# RGBLEDMatrixBPack.net
KiCad netlist of a schematic drawn in EAGLE
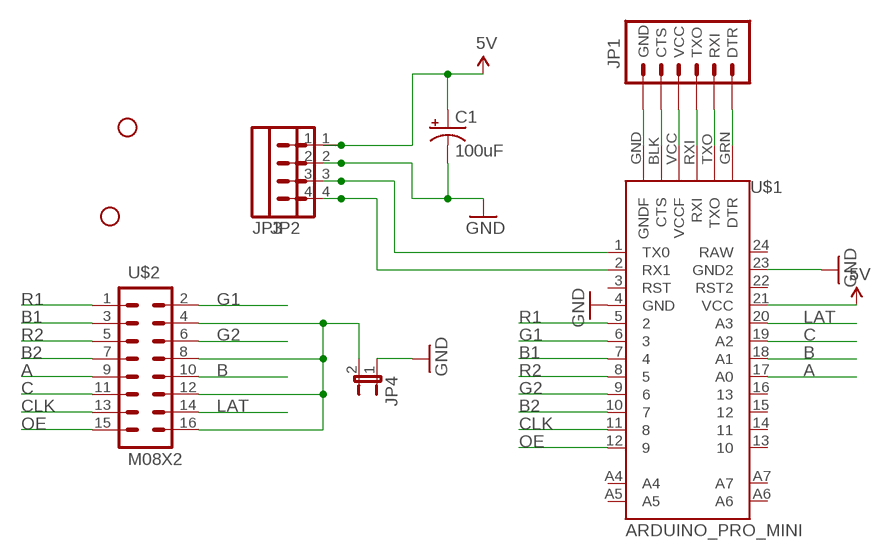
[diagram p0: schematic, sheet 1]

(export (version "E")
  (design (tool "Eeschema 10.0.6"))
  (components
    (comp (ref "C1")
      (value "100uF")
      (footprint "eagle-import:CPOL-RADIAL-100UF-25V")
      (libsource (lib "eagle-import") (part "CAP_POLPTH1"))
    )
    (comp (ref "JP1")
      (value "ARDUINO_SERIAL_PROGRAMPTH")
      (footprint "eagle-import:1X06")
      (libsource (lib "eagle-import") (part "ARDUINO_SERIAL_PROGRAMPTH"))
    )
    (comp (ref "JP2")
      (value "M04JST-PTH")
      (footprint "eagle-import:JST-4-PTH")
      (libsource (lib "eagle-import") (part "M04JST-PTH"))
    )
    (comp (ref "JP3")
      (value "M04JST-PTH")
      (footprint "eagle-import:JST-4-PTH")
      (libsource (lib "eagle-import") (part "M04JST-PTH"))
    )
    (comp (ref "JP4")
      (value "JUMPER-2SMD-NO")
      (footprint "eagle-import:SJ_2S-NO")
      (libsource (lib "eagle-import") (part "JUMPER-2SMD-NO"))
    )
    (comp (ref "STANDOFF1")
      (value "STAND-OFF")
      (footprint "eagle-import:STAND-OFF")
      (libsource (lib "eagle-import") (part "STAND-OFF"))
    )
    (comp (ref "STANDOFF2")
      (value "STAND-OFF")
      (footprint "eagle-import:STAND-OFF")
      (libsource (lib "eagle-import") (part "STAND-OFF"))
    )
    (comp (ref "U$1")
      (value "ARDUINO_PRO_MINI")
      (footprint "eagle-import:ARDUINO_PRO_MINI")
      (libsource (lib "eagle-import") (part "ARDUINO_PRO_MINI"))
    )
    (comp (ref "U$2")
      (value "M08X2")
      (footprint "eagle-import:2X8")
      (libsource (lib "eagle-import") (part "M08X2"))
    )
  )
  (nets
    (net (code "1") (name "/A") (class "Default")
      (node (ref "U$1") (pin "17") (pinfunction "A0_17") (pintype "bidirectional"))
      (node (ref "U$2") (pin "9") (pinfunction "9_9") (pintype "passive"))
    )
    (net (code "2") (name "/B") (class "Default")
      (node (ref "U$1") (pin "18") (pinfunction "A1_18") (pintype "bidirectional"))
      (node (ref "U$2") (pin "10") (pinfunction "10_10") (pintype "passive"))
    )
    (net (code "3") (name "/B1") (class "Default")
      (node (ref "U$1") (pin "7") (pinfunction "4_7") (pintype "bidirectional"))
      (node (ref "U$2") (pin "3") (pinfunction "3_3") (pintype "passive"))
    )
    (net (code "4") (name "/B2") (class "Default")
      (node (ref "U$1") (pin "10") (pinfunction "7_10") (pintype "bidirectional"))
      (node (ref "U$2") (pin "7") (pinfunction "7_7") (pintype "passive"))
    )
    (net (code "5") (name "/C") (class "Default")
      (node (ref "U$1") (pin "19") (pinfunction "A2_19") (pintype "bidirectional"))
      (node (ref "U$2") (pin "11") (pinfunction "11_11") (pintype "passive"))
    )
    (net (code "6") (name "/CLK") (class "Default")
      (node (ref "U$1") (pin "11") (pinfunction "8_11") (pintype "bidirectional"))
      (node (ref "U$2") (pin "13") (pinfunction "13_13") (pintype "passive"))
    )
    (net (code "7") (name "/G1") (class "Default")
      (node (ref "U$1") (pin "6") (pinfunction "3_6") (pintype "bidirectional"))
      (node (ref "U$2") (pin "2") (pinfunction "2_2") (pintype "passive"))
    )
    (net (code "8") (name "/G2") (class "Default")
      (node (ref "U$1") (pin "9") (pinfunction "6_9") (pintype "bidirectional"))
      (node (ref "U$2") (pin "6") (pinfunction "6_6") (pintype "passive"))
    )
    (net (code "9") (name "/LAT") (class "Default")
      (node (ref "U$1") (pin "20") (pinfunction "A3_20") (pintype "bidirectional"))
      (node (ref "U$2") (pin "14") (pinfunction "14_14") (pintype "passive"))
    )
    (net (code "10") (name "/OE") (class "Default")
      (node (ref "U$1") (pin "12") (pinfunction "9_12") (pintype "bidirectional"))
      (node (ref "U$2") (pin "15") (pinfunction "15_15") (pintype "passive"))
    )
    (net (code "11") (name "/R1") (class "Default")
      (node (ref "U$1") (pin "5") (pinfunction "2_5") (pintype "bidirectional"))
      (node (ref "U$2") (pin "1") (pinfunction "1_1") (pintype "passive"))
    )
    (net (code "12") (name "/R2") (class "Default")
      (node (ref "U$1") (pin "8") (pinfunction "5_8") (pintype "bidirectional"))
      (node (ref "U$2") (pin "5") (pinfunction "5_5") (pintype "passive"))
    )
    (net (code "13") (name "5V") (class "Default")
      (node (ref "C1") (pin "1") (pinfunction "+_1") (pintype "passive"))
      (node (ref "JP2") (pin "1") (pinfunction "1_1") (pintype "passive"))
      (node (ref "JP3") (pin "1") (pinfunction "1_1") (pintype "passive"))
      (node (ref "U$1") (pin "21") (pinfunction "VCC_21") (pintype "bidirectional"))
    )
    (net (code "14") (name "GND") (class "Default")
      (node (ref "C1") (pin "2") (pinfunction "-_2") (pintype "passive"))
      (node (ref "JP2") (pin "2") (pinfunction "2_2") (pintype "passive"))
      (node (ref "JP3") (pin "2") (pinfunction "2_2") (pintype "passive"))
      (node (ref "JP4") (pin "1") (pinfunction "1_1") (pintype "passive"))
      (node (ref "U$1") (pin "23") (pinfunction "GND2_23") (pintype "bidirectional"))
      (node (ref "U$1") (pin "4") (pinfunction "GND_4") (pintype "bidirectional"))
    )
    (net (code "15") (name "Net-(JP1-CTS)") (class "Default")
      (node (ref "JP1") (pin "5") (pinfunction "CTS_5") (pintype "passive"))
      (node (ref "U$1") (pin "BLK") (pinfunction "CTS_BLK") (pintype "bidirectional"))
    )
    (net (code "16") (name "Net-(JP1-DTR)") (class "Default")
      (node (ref "JP1") (pin "1") (pinfunction "DTR_1") (pintype "passive"))
      (node (ref "U$1") (pin "GRN") (pinfunction "DTR_GRN") (pintype "bidirectional"))
    )
    (net (code "17") (name "Net-(JP1-GND)") (class "Default")
      (node (ref "JP1") (pin "6") (pinfunction "GND_6") (pintype "passive"))
      (node (ref "U$1") (pin "GND") (pinfunction "GNDF_GND") (pintype "bidirectional"))
    )
    (net (code "18") (name "Net-(JP1-RXI)") (class "Default")
      (node (ref "JP1") (pin "2") (pinfunction "RXI_2") (pintype "passive"))
      (node (ref "U$1") (pin "TXO") (pinfunction "TXO_TXO") (pintype "bidirectional"))
    )
    (net (code "19") (name "Net-(JP1-TXO)") (class "Default")
      (node (ref "JP1") (pin "3") (pinfunction "TXO_3") (pintype "passive"))
      (node (ref "U$1") (pin "RXI") (pinfunction "RXI_RXI") (pintype "bidirectional"))
    )
    (net (code "20") (name "Net-(JP1-VCC)") (class "Default")
      (node (ref "JP1") (pin "4") (pinfunction "VCC_4") (pintype "passive"))
      (node (ref "U$1") (pin "VCC") (pinfunction "VCCF_VCC") (pintype "bidirectional"))
    )
    (net (code "21") (name "Net-(JP4-Pad2)") (class "Default")
      (node (ref "JP4") (pin "2") (pinfunction "2_2") (pintype "passive"))
      (node (ref "U$2") (pin "12") (pinfunction "12_12") (pintype "passive"))
      (node (ref "U$2") (pin "16") (pinfunction "16_16") (pintype "passive"))
      (node (ref "U$2") (pin "4") (pinfunction "4_4") (pintype "passive"))
      (node (ref "U$2") (pin "8") (pinfunction "8_8") (pintype "passive"))
    )
    (net (code "22") (name "Net-(U$1-RX1)") (class "Default")
      (node (ref "JP2") (pin "4") (pinfunction "4_4") (pintype "passive"))
      (node (ref "JP3") (pin "4") (pinfunction "4_4") (pintype "passive"))
      (node (ref "U$1") (pin "2") (pinfunction "RX1_2") (pintype "bidirectional"))
    )
    (net (code "23") (name "Net-(U$1-TX0)") (class "Default")
      (node (ref "JP2") (pin "3") (pinfunction "3_3") (pintype "passive"))
      (node (ref "JP3") (pin "3") (pinfunction "3_3") (pintype "passive"))
      (node (ref "U$1") (pin "1") (pinfunction "TX0_1") (pintype "bidirectional"))
    )
    (net (code "24") (name "unconnected-(U$1-10-Pad13)") (class "Default")
      (node (ref "U$1") (pin "13") (pinfunction "10_13") (pintype "bidirectional"))
    )
    (net (code "25") (name "unconnected-(U$1-11-Pad14)") (class "Default")
      (node (ref "U$1") (pin "14") (pinfunction "11_14") (pintype "bidirectional"))
    )
    (net (code "26") (name "unconnected-(U$1-12-Pad15)") (class "Default")
      (node (ref "U$1") (pin "15") (pinfunction "12_15") (pintype "bidirectional"))
    )
    (net (code "27") (name "unconnected-(U$1-13-Pad16)") (class "Default")
      (node (ref "U$1") (pin "16") (pinfunction "13_16") (pintype "bidirectional"))
    )
    (net (code "28") (name "unconnected-(U$1-PadA4)") (class "Default")
      (node (ref "U$1") (pin "A4") (pinfunction "A4_A4") (pintype "bidirectional"))
    )
    (net (code "29") (name "unconnected-(U$1-PadA5)") (class "Default")
      (node (ref "U$1") (pin "A5") (pinfunction "A5_A5") (pintype "bidirectional"))
    )
    (net (code "30") (name "unconnected-(U$1-PadA6)") (class "Default")
      (node (ref "U$1") (pin "A6") (pinfunction "A6_A6") (pintype "bidirectional"))
    )
    (net (code "31") (name "unconnected-(U$1-PadA7)") (class "Default")
      (node (ref "U$1") (pin "A7") (pinfunction "A7_A7") (pintype "bidirectional"))
    )
    (net (code "32") (name "unconnected-(U$1-RAW-Pad24)") (class "Default")
      (node (ref "U$1") (pin "24") (pinfunction "RAW_24") (pintype "bidirectional"))
    )
    (net (code "33") (name "unconnected-(U$1-RST-Pad3)") (class "Default")
      (node (ref "U$1") (pin "3") (pinfunction "RST_3") (pintype "bidirectional"))
    )
    (net (code "34") (name "unconnected-(U$1-RST2-Pad22)") (class "Default")
      (node (ref "U$1") (pin "22") (pinfunction "RST2_22") (pintype "bidirectional"))
    )
  )
)
